# MCU.net
KiCad netlist of a schematic drawn in Altium Designer
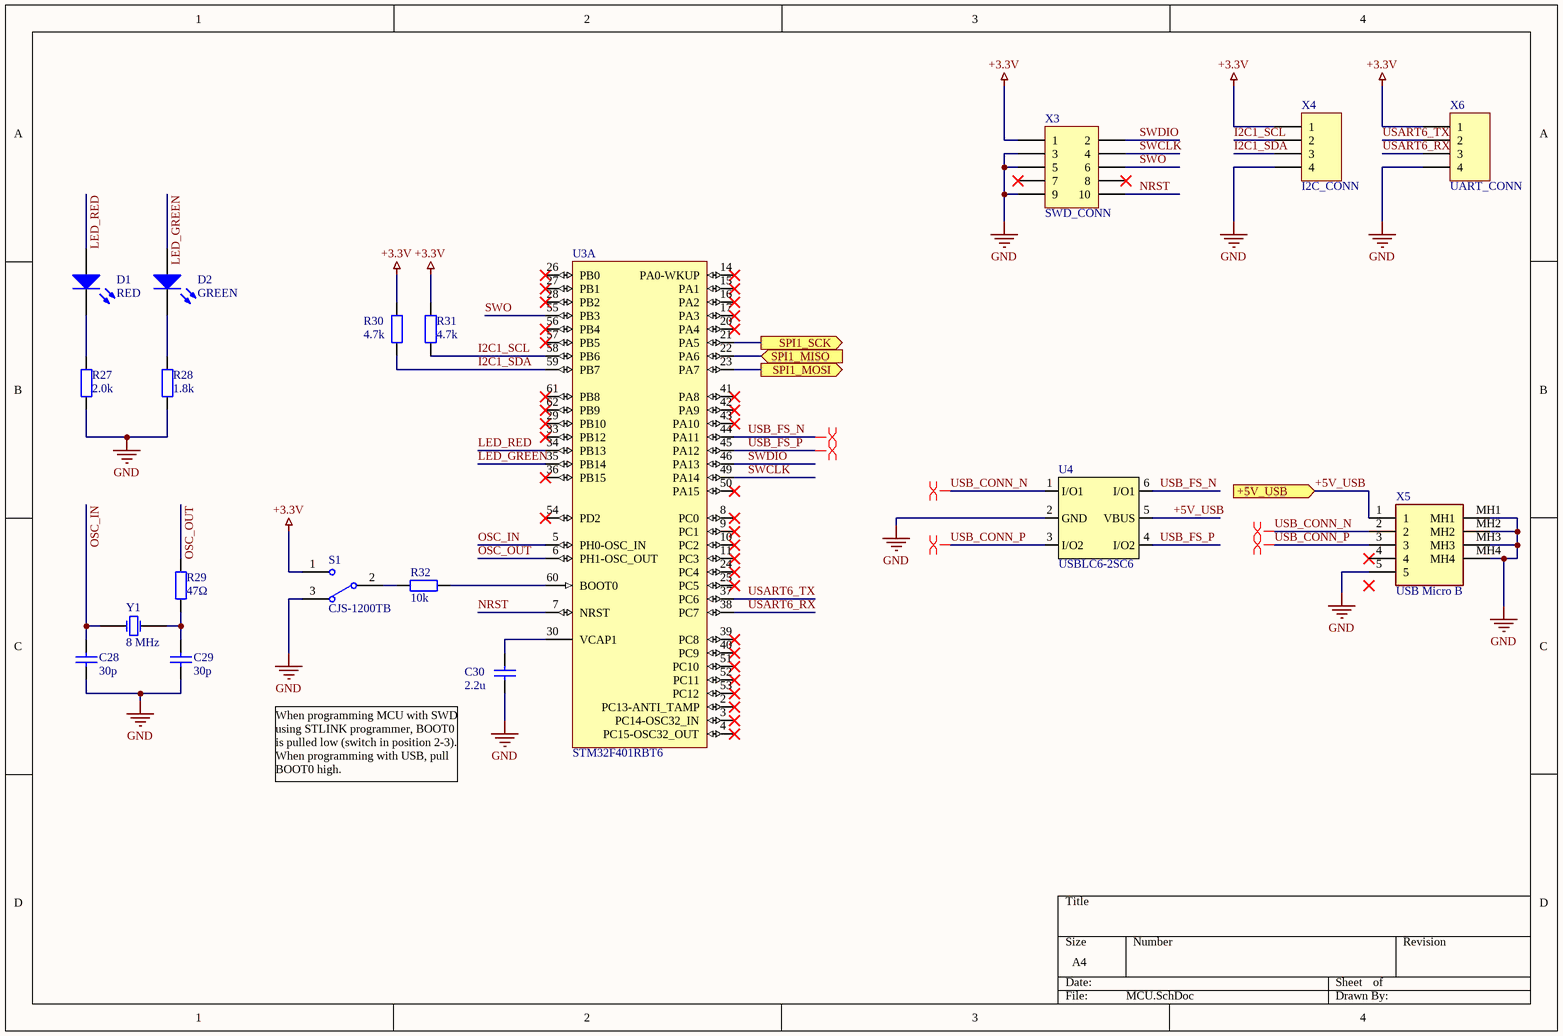
[diagram p0: MCU.SchDoc]

(export (version "E")
  (design (tool "Eeschema 10.0.6"))
  (components
    (comp (ref "C28")
      (value "30p")
      (footprint "CAPC1608X87N")
      (libsource (lib "Miscellaneous Devices") (part "Cap"))
    )
    (comp (ref "C29")
      (value "30p")
      (footprint "CAPC1608X87N")
      (libsource (lib "Miscellaneous Devices") (part "Cap"))
    )
    (comp (ref "C30")
      (value "2.2u")
      (footprint "CAPC2012X110N")
      (libsource (lib "Miscellaneous Devices") (part "Cap"))
    )
    (comp (ref "D1")
      (value "RED")
      (footprint "LEDC2012X110N")
      (libsource (lib "Miscellaneous Devices") (part "LED1"))
    )
    (comp (ref "D2")
      (value "GREEN")
      (footprint "LEDC2012X110N")
      (libsource (lib "Miscellaneous Devices") (part "LED1"))
    )
    (comp (ref "R27")
      (value "2.0k")
      (footprint "RESC1608X55N")
      (libsource (lib "Miscellaneous Devices") (part "Res2"))
    )
    (comp (ref "R28")
      (value "1.8k")
      (footprint "RESC1608X55N")
      (libsource (lib "Miscellaneous Devices") (part "Res2"))
    )
    (comp (ref "R29")
      (value "47Ω")
      (footprint "RESC1608X55N")
      (libsource (lib "Miscellaneous Devices") (part "Res2"))
    )
    (comp (ref "R30")
      (value "4.7k")
      (footprint "RESC1608X55N")
      (libsource (lib "Miscellaneous Devices") (part "Res2"))
    )
    (comp (ref "R31")
      (value "4.7k")
      (footprint "RESC1608X55N")
      (libsource (lib "Miscellaneous Devices") (part "Res2"))
    )
    (comp (ref "R32")
      (value "10k")
      (footprint "RESC1608X55N")
      (fields (field (name "MOUSER PART NUMBER") "603-RC0603FR-0710KL"))
      (libsource (lib "") (part "Res2_1"))
    )
    (comp (ref "S1")
      (value "CJS-1200TB")
      (footprint "B-TYPE")
      (libsource (lib "Miscellaneous Devices") (part "SW-SPDT"))
    )
    (comp (ref "U3")
      (value "STM32F401RBT6")
      (footprint "QFP50P1200X1200X160-64N")
      (libsource (lib "STMicroelectronics STM32 F4") (part "STM32F401RBT6"))
    )
    (comp (ref "U4")
      (value "USBLC6-2SC6")
      (footprint "SOT95P280X145-6N")
      (libsource (lib "Custom_Lib") (part "USBLC6"))
    )
    (comp (ref "X3")
      (value "SWD_CONN")
      (footprint "SHDR10W55P200_2X5_1265X630X640P")
      (libsource (lib "Miscellaneous Connectors") (part "Header 5X2"))
    )
    (comp (ref "X4")
      (value "I2C_CONN")
      (footprint "SHDR4W65P0X254_1X4_1262X660X1216P")
      (libsource (lib "Miscellaneous Connectors") (part "Header 4"))
    )
    (comp (ref "X5")
      (value "USB Micro B")
      (footprint "SamacSys:UJ2MIBH24SMTTR")
      (description "Connector")
      (fields
        (field (name "MOUSER2 PART NUMBER") "490-UJ2-MIBH2-4-SMT")
        (field (name "MANUFACTURER_PART_NUMBER") "UJ2-MIBH2-4-SMT-TR")
      )
      (libsource (lib "*") (part "UJ2-MIBH2-4-SMT-TR"))
    )
    (comp (ref "X6")
      (value "UART_CONN")
      (footprint "SHDR4W65P0X254_1X4_1262X660X1216P")
      (libsource (lib "Miscellaneous Connectors") (part "Header 4"))
    )
    (comp (ref "Y1")
      (value "8 MHz")
      (footprint "ECS080185PXJESTR")
      (libsource (lib "Miscellaneous Devices") (part "XTAL"))
    )
  )
  (nets
    (net (code "1") (name "+3.3V") (class "Default")
      (node (ref "R30") (pin "2") (pinfunction "2_2") (pintype "passive"))
      (node (ref "R31") (pin "2") (pinfunction "2_2") (pintype "passive"))
      (node (ref "S1") (pin "1") (pinfunction "1_1") (pintype "passive"))
      (node (ref "X3") (pin "1") (pinfunction "1_1") (pintype "passive"))
      (node (ref "X4") (pin "1") (pinfunction "1_1") (pintype "passive"))
      (node (ref "X6") (pin "1") (pinfunction "1_1") (pintype "passive"))
    )
    (net (code "2") (name "/+5V_USB") (class "Default")
      (node (ref "U4") (pin "5") (pinfunction "VBUS_5") (pintype "passive"))
      (node (ref "X5") (pin "1") (pinfunction "1_1") (pintype "passive"))
    )
    (net (code "3") (name "/I2C1_SCL") (class "Default")
      (node (ref "R31") (pin "1") (pinfunction "1_1") (pintype "passive"))
      (node (ref "U3") (pin "58") (pinfunction "PB6_58") (pintype "bidirectional"))
      (node (ref "X4") (pin "2") (pinfunction "2_2") (pintype "passive"))
    )
    (net (code "4") (name "/I2C1_SDA") (class "Default")
      (node (ref "R30") (pin "1") (pinfunction "1_1") (pintype "passive"))
      (node (ref "U3") (pin "59") (pinfunction "PB7_59") (pintype "bidirectional"))
      (node (ref "X4") (pin "3") (pinfunction "3_3") (pintype "passive"))
    )
    (net (code "5") (name "/LED_GREEN") (class "Default")
      (node (ref "D2") (pin "1") (pinfunction "A_1") (pintype "passive"))
      (node (ref "U3") (pin "35") (pinfunction "PB14_35") (pintype "bidirectional"))
    )
    (net (code "6") (name "/LED_RED") (class "Default")
      (node (ref "D1") (pin "1") (pinfunction "A_1") (pintype "passive"))
      (node (ref "U3") (pin "34") (pinfunction "PB13_34") (pintype "bidirectional"))
    )
    (net (code "7") (name "/NRST") (class "Default")
      (node (ref "U3") (pin "7") (pinfunction "NRST_7") (pintype "bidirectional"))
      (node (ref "X3") (pin "10") (pinfunction "10_10") (pintype "passive"))
    )
    (net (code "8") (name "/OSC_IN") (class "Default")
      (node (ref "C28") (pin "2") (pinfunction "2_2") (pintype "passive"))
      (node (ref "U3") (pin "5") (pinfunction "PH0-OSC_IN_5") (pintype "bidirectional"))
      (node (ref "Y1") (pin "1") (pinfunction "OSC1_1") (pintype "passive"))
    )
    (net (code "9") (name "/OSC_OUT") (class "Default")
      (node (ref "R29") (pin "2") (pinfunction "2_2") (pintype "passive"))
      (node (ref "U3") (pin "6") (pinfunction "PH1-OSC_OUT_6") (pintype "bidirectional"))
    )
    (net (code "10") (name "/SPI1_MISO") (class "Default")
      (node (ref "U3") (pin "22") (pinfunction "PA6_22") (pintype "bidirectional"))
    )
    (net (code "11") (name "/SPI1_MOSI") (class "Default")
      (node (ref "U3") (pin "23") (pinfunction "PA7_23") (pintype "bidirectional"))
    )
    (net (code "12") (name "/SPI1_SCK") (class "Default")
      (node (ref "U3") (pin "21") (pinfunction "PA5_21") (pintype "bidirectional"))
    )
    (net (code "13") (name "/SWCLK") (class "Default")
      (node (ref "U3") (pin "49") (pinfunction "PA14_49") (pintype "bidirectional"))
      (node (ref "X3") (pin "4") (pinfunction "4_4") (pintype "passive"))
    )
    (net (code "14") (name "/SWDIO") (class "Default")
      (node (ref "U3") (pin "46") (pinfunction "PA13_46") (pintype "bidirectional"))
      (node (ref "X3") (pin "2") (pinfunction "2_2") (pintype "passive"))
    )
    (net (code "15") (name "/SWO") (class "Default")
      (node (ref "U3") (pin "55") (pinfunction "PB3_55") (pintype "bidirectional"))
      (node (ref "X3") (pin "6") (pinfunction "6_6") (pintype "passive"))
    )
    (net (code "16") (name "/USART6_RX") (class "Default")
      (node (ref "U3") (pin "38") (pinfunction "PC7_38") (pintype "bidirectional"))
      (node (ref "X6") (pin "3") (pinfunction "3_3") (pintype "passive"))
    )
    (net (code "17") (name "/USART6_TX") (class "Default")
      (node (ref "U3") (pin "37") (pinfunction "PC6_37") (pintype "bidirectional"))
      (node (ref "X6") (pin "2") (pinfunction "2_2") (pintype "passive"))
    )
    (net (code "18") (name "/USB_CONN_N") (class "Default")
      (node (ref "U4") (pin "1") (pinfunction "I/O1_1") (pintype "passive"))
      (node (ref "X5") (pin "2") (pinfunction "2_2") (pintype "passive"))
    )
    (net (code "19") (name "/USB_CONN_P") (class "Default")
      (node (ref "U4") (pin "3") (pinfunction "I/O2_3") (pintype "passive"))
      (node (ref "X5") (pin "3") (pinfunction "3_3") (pintype "passive"))
    )
    (net (code "20") (name "/USB_FS_N") (class "Default")
      (node (ref "U3") (pin "44") (pinfunction "PA11_44") (pintype "bidirectional"))
      (node (ref "U4") (pin "6") (pinfunction "I/O1_6") (pintype "passive"))
    )
    (net (code "21") (name "/USB_FS_P") (class "Default")
      (node (ref "U3") (pin "45") (pinfunction "PA12_45") (pintype "bidirectional"))
      (node (ref "U4") (pin "4") (pinfunction "I/O2_4") (pintype "passive"))
    )
    (net (code "22") (name "GND") (class "Default")
      (node (ref "C28") (pin "1") (pinfunction "1_1") (pintype "passive"))
      (node (ref "C29") (pin "1") (pinfunction "1_1") (pintype "passive"))
      (node (ref "C30") (pin "1") (pinfunction "1_1") (pintype "passive"))
      (node (ref "R27") (pin "1") (pinfunction "1_1") (pintype "passive"))
      (node (ref "R28") (pin "1") (pinfunction "1_1") (pintype "passive"))
      (node (ref "S1") (pin "3") (pinfunction "3_3") (pintype "passive"))
      (node (ref "U4") (pin "2") (pinfunction "GND_2") (pintype "passive"))
      (node (ref "X3") (pin "3") (pinfunction "3_3") (pintype "passive"))
      (node (ref "X3") (pin "5") (pinfunction "5_5") (pintype "passive"))
      (node (ref "X3") (pin "9") (pinfunction "9_9") (pintype "passive"))
      (node (ref "X4") (pin "4") (pinfunction "4_4") (pintype "passive"))
      (node (ref "X5") (pin "5") (pinfunction "5_5") (pintype "passive"))
      (node (ref "X5") (pin "MH1") (pinfunction "MH1_MH1") (pintype "passive"))
      (node (ref "X5") (pin "MH2") (pinfunction "MH2_MH2") (pintype "passive"))
      (node (ref "X5") (pin "MH3") (pinfunction "MH3_MH3") (pintype "passive"))
      (node (ref "X5") (pin "MH4") (pinfunction "MH4_MH4") (pintype "passive"))
      (node (ref "X6") (pin "4") (pinfunction "4_4") (pintype "passive"))
    )
    (net (code "23") (name "Net-(D1-K)") (class "Default")
      (node (ref "D1") (pin "2") (pinfunction "K_2") (pintype "passive"))
      (node (ref "R27") (pin "2") (pinfunction "2_2") (pintype "passive"))
    )
    (net (code "24") (name "Net-(D2-K)") (class "Default")
      (node (ref "D2") (pin "2") (pinfunction "K_2") (pintype "passive"))
      (node (ref "R28") (pin "2") (pinfunction "2_2") (pintype "passive"))
    )
    (net (code "25") (name "Net-(R32-Pad2)") (class "Default")
      (node (ref "R32") (pin "2") (pinfunction "2_2") (pintype "passive"))
      (node (ref "S1") (pin "2") (pinfunction "2_2") (pintype "passive"))
    )
    (net (code "26") (name "Net-(U3A-BOOT0)") (class "Default")
      (node (ref "R32") (pin "1") (pinfunction "1_1") (pintype "passive"))
      (node (ref "U3") (pin "60") (pinfunction "BOOT0_60") (pintype "input"))
    )
    (net (code "27") (name "Net-(U3A-VCAP1)") (class "Default")
      (node (ref "C30") (pin "2") (pinfunction "2_2") (pintype "passive"))
      (node (ref "U3") (pin "30") (pinfunction "VCAP1_30") (pintype "power_in"))
    )
    (net (code "28") (name "Net-(Y1-OSC2)") (class "Default")
      (node (ref "C29") (pin "2") (pinfunction "2_2") (pintype "passive"))
      (node (ref "R29") (pin "1") (pinfunction "1_1") (pintype "passive"))
      (node (ref "Y1") (pin "2") (pinfunction "OSC2_2") (pintype "passive"))
    )
    (net (code "29") (name "unconnected-(U3A-PA0-WKUP-Pad14)") (class "Default")
      (node (ref "U3") (pin "14") (pinfunction "PA0-WKUP_14") (pintype "bidirectional+no_connect"))
    )
    (net (code "30") (name "unconnected-(U3A-PA1-Pad15)") (class "Default")
      (node (ref "U3") (pin "15") (pinfunction "PA1_15") (pintype "bidirectional+no_connect"))
    )
    (net (code "31") (name "unconnected-(U3A-PA2-Pad16)") (class "Default")
      (node (ref "U3") (pin "16") (pinfunction "PA2_16") (pintype "bidirectional+no_connect"))
    )
    (net (code "32") (name "unconnected-(U3A-PA3-Pad17)") (class "Default")
      (node (ref "U3") (pin "17") (pinfunction "PA3_17") (pintype "bidirectional+no_connect"))
    )
    (net (code "33") (name "unconnected-(U3A-PA4-Pad20)") (class "Default")
      (node (ref "U3") (pin "20") (pinfunction "PA4_20") (pintype "bidirectional+no_connect"))
    )
    (net (code "34") (name "unconnected-(U3A-PA8-Pad41)") (class "Default")
      (node (ref "U3") (pin "41") (pinfunction "PA8_41") (pintype "bidirectional+no_connect"))
    )
    (net (code "35") (name "unconnected-(U3A-PA9-Pad42)") (class "Default")
      (node (ref "U3") (pin "42") (pinfunction "PA9_42") (pintype "bidirectional+no_connect"))
    )
    (net (code "36") (name "unconnected-(U3A-PA10-Pad43)") (class "Default")
      (node (ref "U3") (pin "43") (pinfunction "PA10_43") (pintype "bidirectional+no_connect"))
    )
    (net (code "37") (name "unconnected-(U3A-PA15-Pad50)") (class "Default")
      (node (ref "U3") (pin "50") (pinfunction "PA15_50") (pintype "bidirectional+no_connect"))
    )
    (net (code "38") (name "unconnected-(U3A-PB0-Pad26)") (class "Default")
      (node (ref "U3") (pin "26") (pinfunction "PB0_26") (pintype "bidirectional+no_connect"))
    )
    (net (code "39") (name "unconnected-(U3A-PB1-Pad27)") (class "Default")
      (node (ref "U3") (pin "27") (pinfunction "PB1_27") (pintype "bidirectional+no_connect"))
    )
    (net (code "40") (name "unconnected-(U3A-PB2-Pad28)") (class "Default")
      (node (ref "U3") (pin "28") (pinfunction "PB2_28") (pintype "bidirectional+no_connect"))
    )
    (net (code "41") (name "unconnected-(U3A-PB4-Pad56)") (class "Default")
      (node (ref "U3") (pin "56") (pinfunction "PB4_56") (pintype "bidirectional+no_connect"))
    )
    (net (code "42") (name "unconnected-(U3A-PB5-Pad57)") (class "Default")
      (node (ref "U3") (pin "57") (pinfunction "PB5_57") (pintype "bidirectional+no_connect"))
    )
    (net (code "43") (name "unconnected-(U3A-PB8-Pad61)") (class "Default")
      (node (ref "U3") (pin "61") (pinfunction "PB8_61") (pintype "bidirectional+no_connect"))
    )
    (net (code "44") (name "unconnected-(U3A-PB9-Pad62)") (class "Default")
      (node (ref "U3") (pin "62") (pinfunction "PB9_62") (pintype "bidirectional+no_connect"))
    )
    (net (code "45") (name "unconnected-(U3A-PB10-Pad29)") (class "Default")
      (node (ref "U3") (pin "29") (pinfunction "PB10_29") (pintype "bidirectional+no_connect"))
    )
    (net (code "46") (name "unconnected-(U3A-PB12-Pad33)") (class "Default")
      (node (ref "U3") (pin "33") (pinfunction "PB12_33") (pintype "bidirectional+no_connect"))
    )
    (net (code "47") (name "unconnected-(U3A-PB15-Pad36)") (class "Default")
      (node (ref "U3") (pin "36") (pinfunction "PB15_36") (pintype "bidirectional+no_connect"))
    )
    (net (code "48") (name "unconnected-(U3A-PC0-Pad8)") (class "Default")
      (node (ref "U3") (pin "8") (pinfunction "PC0_8") (pintype "bidirectional+no_connect"))
    )
    (net (code "49") (name "unconnected-(U3A-PC1-Pad9)") (class "Default")
      (node (ref "U3") (pin "9") (pinfunction "PC1_9") (pintype "bidirectional+no_connect"))
    )
    (net (code "50") (name "unconnected-(U3A-PC2-Pad10)") (class "Default")
      (node (ref "U3") (pin "10") (pinfunction "PC2_10") (pintype "bidirectional+no_connect"))
    )
    (net (code "51") (name "unconnected-(U3A-PC3-Pad11)") (class "Default")
      (node (ref "U3") (pin "11") (pinfunction "PC3_11") (pintype "bidirectional+no_connect"))
    )
    (net (code "52") (name "unconnected-(U3A-PC4-Pad24)") (class "Default")
      (node (ref "U3") (pin "24") (pinfunction "PC4_24") (pintype "bidirectional+no_connect"))
    )
    (net (code "53") (name "unconnected-(U3A-PC5-Pad25)") (class "Default")
      (node (ref "U3") (pin "25") (pinfunction "PC5_25") (pintype "bidirectional+no_connect"))
    )
    (net (code "54") (name "unconnected-(U3A-PC8-Pad39)") (class "Default")
      (node (ref "U3") (pin "39") (pinfunction "PC8_39") (pintype "bidirectional+no_connect"))
    )
    (net (code "55") (name "unconnected-(U3A-PC9-Pad40)") (class "Default")
      (node (ref "U3") (pin "40") (pinfunction "PC9_40") (pintype "bidirectional+no_connect"))
    )
    (net (code "56") (name "unconnected-(U3A-PC10-Pad51)") (class "Default")
      (node (ref "U3") (pin "51") (pinfunction "PC10_51") (pintype "bidirectional+no_connect"))
    )
    (net (code "57") (name "unconnected-(U3A-PC11-Pad52)") (class "Default")
      (node (ref "U3") (pin "52") (pinfunction "PC11_52") (pintype "bidirectional+no_connect"))
    )
    (net (code "58") (name "unconnected-(U3A-PC12-Pad53)") (class "Default")
      (node (ref "U3") (pin "53") (pinfunction "PC12_53") (pintype "bidirectional+no_connect"))
    )
    (net (code "59") (name "unconnected-(U3A-PC13-ANTI_TAMP-Pad2)") (class "Default")
      (node (ref "U3") (pin "2") (pinfunction "PC13-ANTI_TAMP_2") (pintype "bidirectional+no_connect"))
    )
    (net (code "60") (name "unconnected-(U3A-PC14-OSC32_IN-Pad3)") (class "Default")
      (node (ref "U3") (pin "3") (pinfunction "PC14-OSC32_IN_3") (pintype "bidirectional+no_connect"))
    )
    (net (code "61") (name "unconnected-(U3A-PC15-OSC32_OUT-Pad4)") (class "Default")
      (node (ref "U3") (pin "4") (pinfunction "PC15-OSC32_OUT_4") (pintype "bidirectional+no_connect"))
    )
    (net (code "62") (name "unconnected-(U3A-PD2-Pad54)") (class "Default")
      (node (ref "U3") (pin "54") (pinfunction "PD2_54") (pintype "bidirectional+no_connect"))
    )
    (net (code "63") (name "unconnected-(X3-Pad7)") (class "Default")
      (node (ref "X3") (pin "7") (pinfunction "7_7") (pintype "passive+no_connect"))
    )
    (net (code "64") (name "unconnected-(X3-Pad8)") (class "Default")
      (node (ref "X3") (pin "8") (pinfunction "8_8") (pintype "passive+no_connect"))
    )
    (net (code "65") (name "unconnected-(X5-Pad4)") (class "Default")
      (node (ref "X5") (pin "4") (pinfunction "4_4") (pintype "passive+no_connect"))
    )
  )
)
